# DIGITAL2.net
KiCad netlist of a schematic drawn in EAGLE
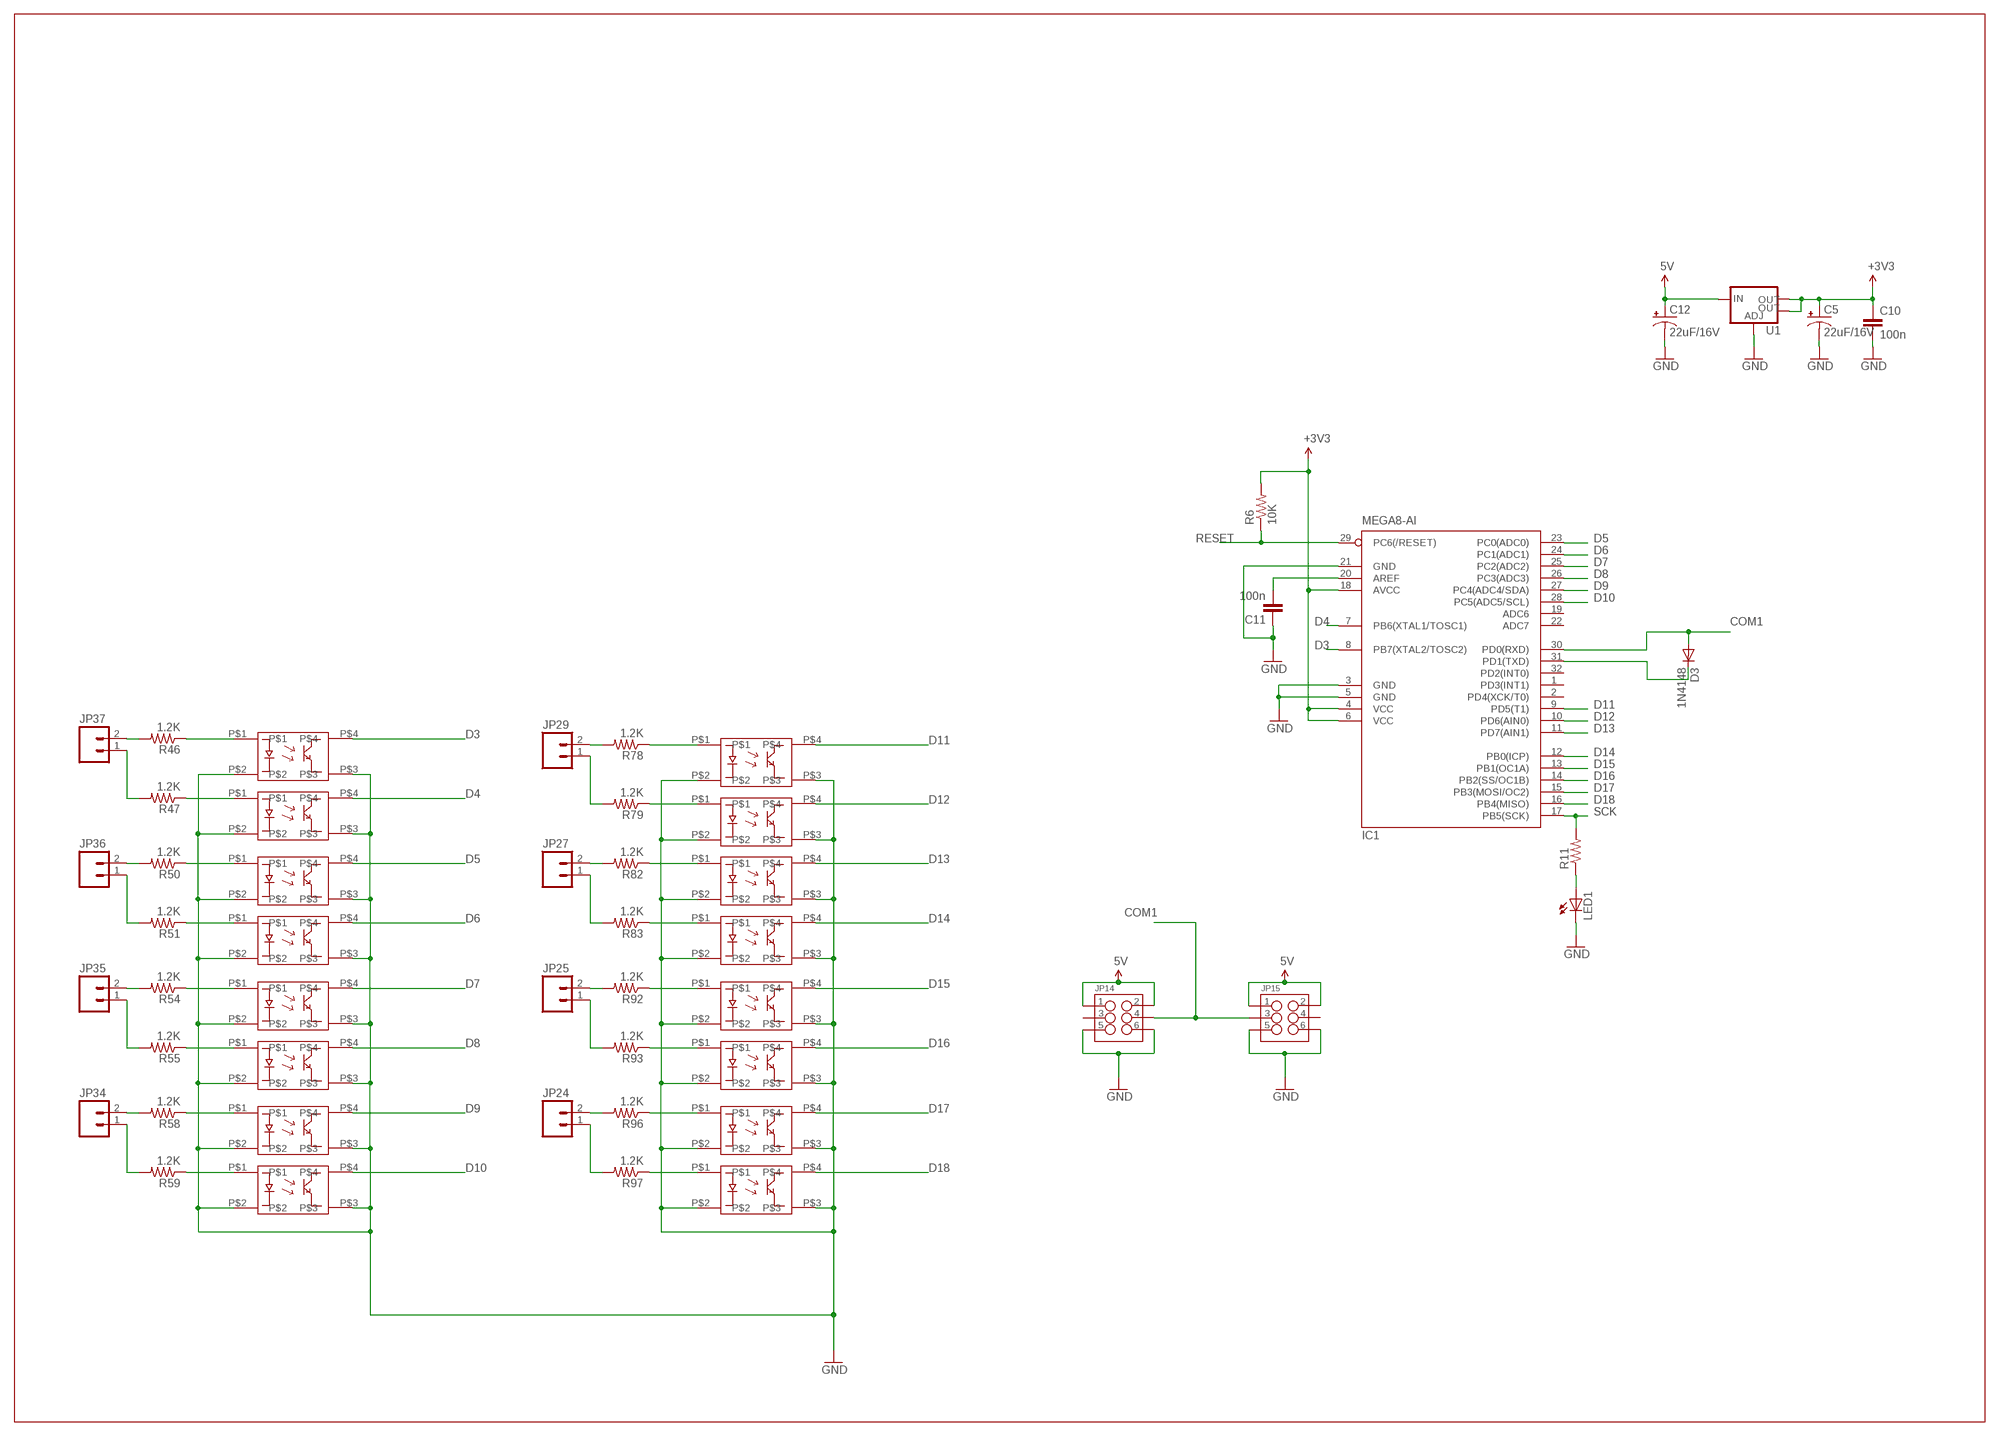
[diagram p0: schematic, sheet 1]

(export (version "E")
  (design (tool "Eeschema 10.0.6"))
  (components
    (comp (ref "C5")
      (value "22uF/16V")
      (footprint "eagle-import:EIA3216")
      (libsource (lib "eagle-import") (part "CAP_POL1206"))
    )
    (comp (ref "C10")
      (value "100n")
      (footprint "eagle-import:0805")
      (libsource (lib "eagle-import") (part "CAP0805"))
    )
    (comp (ref "C11")
      (value "100n")
      (footprint "eagle-import:0805")
      (libsource (lib "eagle-import") (part "CAP0805"))
    )
    (comp (ref "C12")
      (value "22uF/16V")
      (footprint "eagle-import:EIA3216")
      (libsource (lib "eagle-import") (part "CAP_POL1206"))
    )
    (comp (ref "D3")
      (value "1N4148")
      (footprint "eagle-import:MINIMELF")
      (libsource (lib "eagle-import") (part "DIODE-MINIMELF"))
    )
    (comp (ref "IC1")
      (value "MEGA8-AI")
      (footprint "eagle-import:TQFP32-08")
      (fields (field (name "MPN") "ATMEGA8-16AU"))
      (libsource (lib "eagle-import") (part "MEGA8-AI"))
    )
    (comp (ref "JP14")
      (value "M03X22X3_SILK_MALE_PTH")
      (footprint "eagle-import:2X3")
      (libsource (lib "eagle-import") (part "M03X22X3_SILK_MALE_PTH"))
    )
    (comp (ref "JP15")
      (value "M03X22X3_SILK_MALE_PTH")
      (footprint "eagle-import:2X3")
      (libsource (lib "eagle-import") (part "M03X22X3_SILK_MALE_PTH"))
    )
    (comp (ref "JP24")
      (value "M025MM")
      (footprint "eagle-import:SCREWTERMINAL-5MM-2")
      (libsource (lib "eagle-import") (part "M025MM"))
    )
    (comp (ref "JP25")
      (value "M025MM")
      (footprint "eagle-import:SCREWTERMINAL-5MM-2")
      (libsource (lib "eagle-import") (part "M025MM"))
    )
    (comp (ref "JP27")
      (value "M025MM")
      (footprint "eagle-import:SCREWTERMINAL-5MM-2")
      (libsource (lib "eagle-import") (part "M025MM"))
    )
    (comp (ref "JP29")
      (value "M025MM")
      (footprint "eagle-import:SCREWTERMINAL-5MM-2")
      (libsource (lib "eagle-import") (part "M025MM"))
    )
    (comp (ref "JP34")
      (value "M025MM")
      (footprint "eagle-import:SCREWTERMINAL-5MM-2")
      (libsource (lib "eagle-import") (part "M025MM"))
    )
    (comp (ref "JP35")
      (value "M025MM")
      (footprint "eagle-import:SCREWTERMINAL-5MM-2")
      (libsource (lib "eagle-import") (part "M025MM"))
    )
    (comp (ref "JP36")
      (value "M025MM")
      (footprint "eagle-import:SCREWTERMINAL-5MM-2")
      (libsource (lib "eagle-import") (part "M025MM"))
    )
    (comp (ref "JP37")
      (value "M025MM")
      (footprint "eagle-import:SCREWTERMINAL-5MM-2")
      (libsource (lib "eagle-import") (part "M025MM"))
    )
    (comp (ref "LED1")
      (value "LEDCHIP-LED0805")
      (footprint "eagle-import:CHIP-LED0805")
      (libsource (lib "eagle-import") (part "LEDCHIP-LED0805"))
    )
    (comp (ref "R6")
      (value "10K")
      (footprint "eagle-import:0805")
      (libsource (lib "eagle-import") (part "RESISTOR0805-RES"))
    )
    (comp (ref "R11")
      (value "RESISTOR0805-RES")
      (footprint "eagle-import:0805")
      (libsource (lib "eagle-import") (part "RESISTOR0805-RES"))
    )
    (comp (ref "R46")
      (value "1.2K")
      (footprint "eagle-import:1206")
      (libsource (lib "eagle-import") (part "RESISTOR1206"))
    )
    (comp (ref "R47")
      (value "1.2K")
      (footprint "eagle-import:1206")
      (libsource (lib "eagle-import") (part "RESISTOR1206"))
    )
    (comp (ref "R50")
      (value "1.2K")
      (footprint "eagle-import:1206")
      (libsource (lib "eagle-import") (part "RESISTOR1206"))
    )
    (comp (ref "R51")
      (value "1.2K")
      (footprint "eagle-import:1206")
      (libsource (lib "eagle-import") (part "RESISTOR1206"))
    )
    (comp (ref "R54")
      (value "1.2K")
      (footprint "eagle-import:1206")
      (libsource (lib "eagle-import") (part "RESISTOR1206"))
    )
    (comp (ref "R55")
      (value "1.2K")
      (footprint "eagle-import:1206")
      (libsource (lib "eagle-import") (part "RESISTOR1206"))
    )
    (comp (ref "R58")
      (value "1.2K")
      (footprint "eagle-import:1206")
      (libsource (lib "eagle-import") (part "RESISTOR1206"))
    )
    (comp (ref "R59")
      (value "1.2K")
      (footprint "eagle-import:1206")
      (libsource (lib "eagle-import") (part "RESISTOR1206"))
    )
    (comp (ref "R78")
      (value "1.2K")
      (footprint "eagle-import:1206")
      (libsource (lib "eagle-import") (part "RESISTOR1206"))
    )
    (comp (ref "R79")
      (value "1.2K")
      (footprint "eagle-import:1206")
      (libsource (lib "eagle-import") (part "RESISTOR1206"))
    )
    (comp (ref "R82")
      (value "1.2K")
      (footprint "eagle-import:1206")
      (libsource (lib "eagle-import") (part "RESISTOR1206"))
    )
    (comp (ref "R83")
      (value "1.2K")
      (footprint "eagle-import:1206")
      (libsource (lib "eagle-import") (part "RESISTOR1206"))
    )
    (comp (ref "R92")
      (value "1.2K")
      (footprint "eagle-import:1206")
      (libsource (lib "eagle-import") (part "RESISTOR1206"))
    )
    (comp (ref "R93")
      (value "1.2K")
      (footprint "eagle-import:1206")
      (libsource (lib "eagle-import") (part "RESISTOR1206"))
    )
    (comp (ref "R96")
      (value "1.2K")
      (footprint "eagle-import:1206")
      (libsource (lib "eagle-import") (part "RESISTOR1206"))
    )
    (comp (ref "R97")
      (value "1.2K")
      (footprint "eagle-import:1206")
      (libsource (lib "eagle-import") (part "RESISTOR1206"))
    )
    (comp (ref "U$13")
      (value "IS181D-I")
      (footprint "eagle-import:TLP181-I")
      (libsource (lib "eagle-import") (part "IS181D-I"))
    )
    (comp (ref "U$14")
      (value "IS181D-I")
      (footprint "eagle-import:TLP181-I")
      (libsource (lib "eagle-import") (part "IS181D-I"))
    )
    (comp (ref "U$15")
      (value "IS181D-I")
      (footprint "eagle-import:TLP181-I")
      (libsource (lib "eagle-import") (part "IS181D-I"))
    )
    (comp (ref "U$16")
      (value "IS181D-I")
      (footprint "eagle-import:TLP181-I")
      (libsource (lib "eagle-import") (part "IS181D-I"))
    )
    (comp (ref "U$17")
      (value "IS181D-I")
      (footprint "eagle-import:TLP181-I")
      (libsource (lib "eagle-import") (part "IS181D-I"))
    )
    (comp (ref "U$18")
      (value "IS181D-I")
      (footprint "eagle-import:TLP181-I")
      (libsource (lib "eagle-import") (part "IS181D-I"))
    )
    (comp (ref "U$19")
      (value "IS181D-I")
      (footprint "eagle-import:TLP181-I")
      (libsource (lib "eagle-import") (part "IS181D-I"))
    )
    (comp (ref "U$20")
      (value "IS181D-I")
      (footprint "eagle-import:TLP181-I")
      (libsource (lib "eagle-import") (part "IS181D-I"))
    )
    (comp (ref "U$29")
      (value "IS181D-I")
      (footprint "eagle-import:TLP181-I")
      (libsource (lib "eagle-import") (part "IS181D-I"))
    )
    (comp (ref "U$30")
      (value "IS181D-I")
      (footprint "eagle-import:TLP181-I")
      (libsource (lib "eagle-import") (part "IS181D-I"))
    )
    (comp (ref "U$31")
      (value "IS181D-I")
      (footprint "eagle-import:TLP181-I")
      (libsource (lib "eagle-import") (part "IS181D-I"))
    )
    (comp (ref "U$32")
      (value "IS181D-I")
      (footprint "eagle-import:TLP181-I")
      (libsource (lib "eagle-import") (part "IS181D-I"))
    )
    (comp (ref "U$33")
      (value "IS181D-I")
      (footprint "eagle-import:TLP181-I")
      (libsource (lib "eagle-import") (part "IS181D-I"))
    )
    (comp (ref "U$34")
      (value "IS181D-I")
      (footprint "eagle-import:TLP181-I")
      (libsource (lib "eagle-import") (part "IS181D-I"))
    )
    (comp (ref "U$35")
      (value "IS181D-I")
      (footprint "eagle-import:TLP181-I")
      (libsource (lib "eagle-import") (part "IS181D-I"))
    )
    (comp (ref "U$36")
      (value "IS181D-I")
      (footprint "eagle-import:TLP181-I")
      (libsource (lib "eagle-import") (part "IS181D-I"))
    )
    (comp (ref "U1")
      (value "V_REG_LM1117SOT223")
      (footprint "eagle-import:SOT223")
      (libsource (lib "eagle-import") (part "V_REG_LM1117SOT223"))
    )
  )
  (nets
    (net (code "1") (name "+3V3") (class "Default")
      (node (ref "C10") (pin "1") (pinfunction "1_1") (pintype "passive"))
      (node (ref "C5") (pin "A") (pinfunction "+_A") (pintype "passive"))
      (node (ref "IC1") (pin "18") (pinfunction "AVCC_18") (pintype "power_in"))
      (node (ref "IC1") (pin "4") (pinfunction "VCC_4") (pintype "power_in"))
      (node (ref "IC1") (pin "6") (pinfunction "VCC_6") (pintype "power_in"))
      (node (ref "R6") (pin "2") (pinfunction "2_2") (pintype "passive"))
      (node (ref "U1") (pin "2") (pinfunction "OUT_2") (pintype "output"))
      (node (ref "U1") (pin "4") (pinfunction "OUT_4") (pintype "output"))
    )
    (net (code "2") (name "/COM1") (class "Default")
      (node (ref "D3") (pin "A") (pinfunction "A_A") (pintype "passive"))
      (node (ref "IC1") (pin "30") (pinfunction "PD0(RXD)_30") (pintype "bidirectional"))
      (node (ref "JP14") (pin "4") (pinfunction "4_4") (pintype "bidirectional"))
      (node (ref "JP15") (pin "3") (pinfunction "3_3") (pintype "bidirectional"))
    )
    (net (code "3") (name "/D3") (class "Default")
      (node (ref "IC1") (pin "8") (pinfunction "PB7(XTAL2/TOSC2)_8") (pintype "bidirectional"))
      (node (ref "U$13") (pin "P$4") (pinfunction "P$4_P$4") (pintype "bidirectional"))
    )
    (net (code "4") (name "/D4") (class "Default")
      (node (ref "IC1") (pin "7") (pinfunction "PB6(XTAL1/TOSC1)_7") (pintype "bidirectional"))
      (node (ref "U$14") (pin "P$4") (pinfunction "P$4_P$4") (pintype "bidirectional"))
    )
    (net (code "5") (name "/D5") (class "Default")
      (node (ref "IC1") (pin "23") (pinfunction "PC0(ADC0)_23") (pintype "bidirectional"))
      (node (ref "U$15") (pin "P$4") (pinfunction "P$4_P$4") (pintype "bidirectional"))
    )
    (net (code "6") (name "/D6") (class "Default")
      (node (ref "IC1") (pin "24") (pinfunction "PC1(ADC1)_24") (pintype "bidirectional"))
      (node (ref "U$16") (pin "P$4") (pinfunction "P$4_P$4") (pintype "bidirectional"))
    )
    (net (code "7") (name "/D7") (class "Default")
      (node (ref "IC1") (pin "25") (pinfunction "PC2(ADC2)_25") (pintype "bidirectional"))
      (node (ref "U$17") (pin "P$4") (pinfunction "P$4_P$4") (pintype "bidirectional"))
    )
    (net (code "8") (name "/D8") (class "Default")
      (node (ref "IC1") (pin "26") (pinfunction "PC3(ADC3)_26") (pintype "bidirectional"))
      (node (ref "U$18") (pin "P$4") (pinfunction "P$4_P$4") (pintype "bidirectional"))
    )
    (net (code "9") (name "/D9") (class "Default")
      (node (ref "IC1") (pin "27") (pinfunction "PC4(ADC4/SDA)_27") (pintype "bidirectional"))
      (node (ref "U$19") (pin "P$4") (pinfunction "P$4_P$4") (pintype "bidirectional"))
    )
    (net (code "10") (name "/D10") (class "Default")
      (node (ref "IC1") (pin "28") (pinfunction "PC5(ADC5/SCL)_28") (pintype "bidirectional"))
      (node (ref "U$20") (pin "P$4") (pinfunction "P$4_P$4") (pintype "bidirectional"))
    )
    (net (code "11") (name "/D11") (class "Default")
      (node (ref "IC1") (pin "9") (pinfunction "PD5(T1)_9") (pintype "bidirectional"))
      (node (ref "U$29") (pin "P$4") (pinfunction "P$4_P$4") (pintype "bidirectional"))
    )
    (net (code "12") (name "/D12") (class "Default")
      (node (ref "IC1") (pin "10") (pinfunction "PD6(AIN0)_10") (pintype "bidirectional"))
      (node (ref "U$30") (pin "P$4") (pinfunction "P$4_P$4") (pintype "bidirectional"))
    )
    (net (code "13") (name "/D13") (class "Default")
      (node (ref "IC1") (pin "11") (pinfunction "PD7(AIN1)_11") (pintype "bidirectional"))
      (node (ref "U$31") (pin "P$4") (pinfunction "P$4_P$4") (pintype "bidirectional"))
    )
    (net (code "14") (name "/D14") (class "Default")
      (node (ref "IC1") (pin "12") (pinfunction "PB0(ICP)_12") (pintype "bidirectional"))
      (node (ref "U$32") (pin "P$4") (pinfunction "P$4_P$4") (pintype "bidirectional"))
    )
    (net (code "15") (name "/D15") (class "Default")
      (node (ref "IC1") (pin "13") (pinfunction "PB1(OC1A)_13") (pintype "bidirectional"))
      (node (ref "U$33") (pin "P$4") (pinfunction "P$4_P$4") (pintype "bidirectional"))
    )
    (net (code "16") (name "/D16") (class "Default")
      (node (ref "IC1") (pin "14") (pinfunction "PB2(SS/OC1B)_14") (pintype "bidirectional"))
      (node (ref "U$34") (pin "P$4") (pinfunction "P$4_P$4") (pintype "bidirectional"))
    )
    (net (code "17") (name "/D17") (class "Default")
      (node (ref "IC1") (pin "15") (pinfunction "PB3(MOSI/OC2)_15") (pintype "bidirectional"))
      (node (ref "U$35") (pin "P$4") (pinfunction "P$4_P$4") (pintype "bidirectional"))
    )
    (net (code "18") (name "/D18") (class "Default")
      (node (ref "IC1") (pin "16") (pinfunction "PB4(MISO)_16") (pintype "bidirectional"))
      (node (ref "U$36") (pin "P$4") (pinfunction "P$4_P$4") (pintype "bidirectional"))
    )
    (net (code "19") (name "/RESET") (class "Default")
      (node (ref "IC1") (pin "29") (pinfunction "PC6(/RESET)_29") (pintype "bidirectional"))
      (node (ref "R6") (pin "1") (pinfunction "1_1") (pintype "passive"))
    )
    (net (code "20") (name "/SCK") (class "Default")
      (node (ref "IC1") (pin "17") (pinfunction "PB5(SCK)_17") (pintype "bidirectional"))
      (node (ref "R11") (pin "2") (pinfunction "2_2") (pintype "passive"))
    )
    (net (code "21") (name "5V") (class "Default")
      (node (ref "C12") (pin "A") (pinfunction "+_A") (pintype "passive"))
      (node (ref "JP14") (pin "1") (pinfunction "1_1") (pintype "bidirectional"))
      (node (ref "JP14") (pin "2") (pinfunction "2_2") (pintype "bidirectional"))
      (node (ref "JP15") (pin "1") (pinfunction "1_1") (pintype "bidirectional"))
      (node (ref "JP15") (pin "2") (pinfunction "2_2") (pintype "bidirectional"))
      (node (ref "U1") (pin "3") (pinfunction "IN_3") (pintype "input"))
    )
    (net (code "22") (name "GND") (class "Default")
      (node (ref "C10") (pin "2") (pinfunction "2_2") (pintype "passive"))
      (node (ref "C11") (pin "1") (pinfunction "1_1") (pintype "passive"))
      (node (ref "C12") (pin "C") (pinfunction "-_C") (pintype "passive"))
      (node (ref "C5") (pin "C") (pinfunction "-_C") (pintype "passive"))
      (node (ref "IC1") (pin "21") (pinfunction "GND_21") (pintype "power_in"))
      (node (ref "IC1") (pin "3") (pinfunction "GND_3") (pintype "power_in"))
      (node (ref "IC1") (pin "5") (pinfunction "GND_5") (pintype "power_in"))
      (node (ref "JP14") (pin "5") (pinfunction "5_5") (pintype "bidirectional"))
      (node (ref "JP14") (pin "6") (pinfunction "6_6") (pintype "bidirectional"))
      (node (ref "JP15") (pin "5") (pinfunction "5_5") (pintype "bidirectional"))
      (node (ref "JP15") (pin "6") (pinfunction "6_6") (pintype "bidirectional"))
      (node (ref "LED1") (pin "C") (pinfunction "C_C") (pintype "passive"))
      (node (ref "U$13") (pin "P$2") (pinfunction "P$2_P$2") (pintype "bidirectional"))
      (node (ref "U$13") (pin "P$3") (pinfunction "P$3_P$3") (pintype "bidirectional"))
      (node (ref "U$14") (pin "P$2") (pinfunction "P$2_P$2") (pintype "bidirectional"))
      (node (ref "U$14") (pin "P$3") (pinfunction "P$3_P$3") (pintype "bidirectional"))
      (node (ref "U$15") (pin "P$2") (pinfunction "P$2_P$2") (pintype "bidirectional"))
      (node (ref "U$15") (pin "P$3") (pinfunction "P$3_P$3") (pintype "bidirectional"))
      (node (ref "U$16") (pin "P$2") (pinfunction "P$2_P$2") (pintype "bidirectional"))
      (node (ref "U$16") (pin "P$3") (pinfunction "P$3_P$3") (pintype "bidirectional"))
      (node (ref "U$17") (pin "P$2") (pinfunction "P$2_P$2") (pintype "bidirectional"))
      (node (ref "U$17") (pin "P$3") (pinfunction "P$3_P$3") (pintype "bidirectional"))
      (node (ref "U$18") (pin "P$2") (pinfunction "P$2_P$2") (pintype "bidirectional"))
      (node (ref "U$18") (pin "P$3") (pinfunction "P$3_P$3") (pintype "bidirectional"))
      (node (ref "U$19") (pin "P$2") (pinfunction "P$2_P$2") (pintype "bidirectional"))
      (node (ref "U$19") (pin "P$3") (pinfunction "P$3_P$3") (pintype "bidirectional"))
      (node (ref "U$20") (pin "P$2") (pinfunction "P$2_P$2") (pintype "bidirectional"))
      (node (ref "U$20") (pin "P$3") (pinfunction "P$3_P$3") (pintype "bidirectional"))
      (node (ref "U$29") (pin "P$2") (pinfunction "P$2_P$2") (pintype "bidirectional"))
      (node (ref "U$29") (pin "P$3") (pinfunction "P$3_P$3") (pintype "bidirectional"))
      (node (ref "U$30") (pin "P$2") (pinfunction "P$2_P$2") (pintype "bidirectional"))
      (node (ref "U$30") (pin "P$3") (pinfunction "P$3_P$3") (pintype "bidirectional"))
      (node (ref "U$31") (pin "P$2") (pinfunction "P$2_P$2") (pintype "bidirectional"))
      (node (ref "U$31") (pin "P$3") (pinfunction "P$3_P$3") (pintype "bidirectional"))
      (node (ref "U$32") (pin "P$2") (pinfunction "P$2_P$2") (pintype "bidirectional"))
      (node (ref "U$32") (pin "P$3") (pinfunction "P$3_P$3") (pintype "bidirectional"))
      (node (ref "U$33") (pin "P$2") (pinfunction "P$2_P$2") (pintype "bidirectional"))
      (node (ref "U$33") (pin "P$3") (pinfunction "P$3_P$3") (pintype "bidirectional"))
      (node (ref "U$34") (pin "P$2") (pinfunction "P$2_P$2") (pintype "bidirectional"))
      (node (ref "U$34") (pin "P$3") (pinfunction "P$3_P$3") (pintype "bidirectional"))
      (node (ref "U$35") (pin "P$2") (pinfunction "P$2_P$2") (pintype "bidirectional"))
      (node (ref "U$35") (pin "P$3") (pinfunction "P$3_P$3") (pintype "bidirectional"))
      (node (ref "U$36") (pin "P$2") (pinfunction "P$2_P$2") (pintype "bidirectional"))
      (node (ref "U$36") (pin "P$3") (pinfunction "P$3_P$3") (pintype "bidirectional"))
      (node (ref "U1") (pin "1") (pinfunction "ADJ_1") (pintype "input"))
    )
    (net (code "23") (name "Net-(IC1-AREF)") (class "Default")
      (node (ref "C11") (pin "2") (pinfunction "2_2") (pintype "passive"))
      (node (ref "IC1") (pin "20") (pinfunction "AREF_20") (pintype "passive"))
    )
    (net (code "24") (name "Net-(IC1-PD1(TXD))") (class "Default")
      (node (ref "D3") (pin "C") (pinfunction "C_C") (pintype "passive"))
      (node (ref "IC1") (pin "31") (pinfunction "PD1(TXD)_31") (pintype "bidirectional"))
    )
    (net (code "25") (name "Net-(JP24-Pad1)") (class "Default")
      (node (ref "JP24") (pin "1") (pinfunction "1_1") (pintype "passive"))
      (node (ref "R97") (pin "2") (pinfunction "2_2") (pintype "passive"))
    )
    (net (code "26") (name "Net-(JP24-Pad2)") (class "Default")
      (node (ref "JP24") (pin "2") (pinfunction "2_2") (pintype "passive"))
      (node (ref "R96") (pin "2") (pinfunction "2_2") (pintype "passive"))
    )
    (net (code "27") (name "Net-(JP25-Pad1)") (class "Default")
      (node (ref "JP25") (pin "1") (pinfunction "1_1") (pintype "passive"))
      (node (ref "R93") (pin "2") (pinfunction "2_2") (pintype "passive"))
    )
    (net (code "28") (name "Net-(JP25-Pad2)") (class "Default")
      (node (ref "JP25") (pin "2") (pinfunction "2_2") (pintype "passive"))
      (node (ref "R92") (pin "2") (pinfunction "2_2") (pintype "passive"))
    )
    (net (code "29") (name "Net-(JP27-Pad1)") (class "Default")
      (node (ref "JP27") (pin "1") (pinfunction "1_1") (pintype "passive"))
      (node (ref "R83") (pin "2") (pinfunction "2_2") (pintype "passive"))
    )
    (net (code "30") (name "Net-(JP27-Pad2)") (class "Default")
      (node (ref "JP27") (pin "2") (pinfunction "2_2") (pintype "passive"))
      (node (ref "R82") (pin "2") (pinfunction "2_2") (pintype "passive"))
    )
    (net (code "31") (name "Net-(JP29-Pad1)") (class "Default")
      (node (ref "JP29") (pin "1") (pinfunction "1_1") (pintype "passive"))
      (node (ref "R79") (pin "2") (pinfunction "2_2") (pintype "passive"))
    )
    (net (code "32") (name "Net-(JP29-Pad2)") (class "Default")
      (node (ref "JP29") (pin "2") (pinfunction "2_2") (pintype "passive"))
      (node (ref "R78") (pin "2") (pinfunction "2_2") (pintype "passive"))
    )
    (net (code "33") (name "Net-(JP34-Pad1)") (class "Default")
      (node (ref "JP34") (pin "1") (pinfunction "1_1") (pintype "passive"))
      (node (ref "R59") (pin "2") (pinfunction "2_2") (pintype "passive"))
    )
    (net (code "34") (name "Net-(JP34-Pad2)") (class "Default")
      (node (ref "JP34") (pin "2") (pinfunction "2_2") (pintype "passive"))
      (node (ref "R58") (pin "2") (pinfunction "2_2") (pintype "passive"))
    )
    (net (code "35") (name "Net-(JP35-Pad1)") (class "Default")
      (node (ref "JP35") (pin "1") (pinfunction "1_1") (pintype "passive"))
      (node (ref "R55") (pin "2") (pinfunction "2_2") (pintype "passive"))
    )
    (net (code "36") (name "Net-(JP35-Pad2)") (class "Default")
      (node (ref "JP35") (pin "2") (pinfunction "2_2") (pintype "passive"))
      (node (ref "R54") (pin "2") (pinfunction "2_2") (pintype "passive"))
    )
    (net (code "37") (name "Net-(JP36-Pad1)") (class "Default")
      (node (ref "JP36") (pin "1") (pinfunction "1_1") (pintype "passive"))
      (node (ref "R51") (pin "2") (pinfunction "2_2") (pintype "passive"))
    )
    (net (code "38") (name "Net-(JP36-Pad2)") (class "Default")
      (node (ref "JP36") (pin "2") (pinfunction "2_2") (pintype "passive"))
      (node (ref "R50") (pin "2") (pinfunction "2_2") (pintype "passive"))
    )
    (net (code "39") (name "Net-(JP37-Pad1)") (class "Default")
      (node (ref "JP37") (pin "1") (pinfunction "1_1") (pintype "passive"))
      (node (ref "R47") (pin "2") (pinfunction "2_2") (pintype "passive"))
    )
    (net (code "40") (name "Net-(JP37-Pad2)") (class "Default")
      (node (ref "JP37") (pin "2") (pinfunction "2_2") (pintype "passive"))
      (node (ref "R46") (pin "2") (pinfunction "2_2") (pintype "passive"))
    )
    (net (code "41") (name "Net-(LED1-PadA)") (class "Default")
      (node (ref "LED1") (pin "A") (pinfunction "A_A") (pintype "passive"))
      (node (ref "R11") (pin "1") (pinfunction "1_1") (pintype "passive"))
    )
    (net (code "42") (name "Net-(R46-Pad1)") (class "Default")
      (node (ref "R46") (pin "1") (pinfunction "1_1") (pintype "passive"))
      (node (ref "U$13") (pin "P$1") (pinfunction "P$1_P$1") (pintype "bidirectional"))
    )
    (net (code "43") (name "Net-(R47-Pad1)") (class "Default")
      (node (ref "R47") (pin "1") (pinfunction "1_1") (pintype "passive"))
      (node (ref "U$14") (pin "P$1") (pinfunction "P$1_P$1") (pintype "bidirectional"))
    )
    (net (code "44") (name "Net-(R50-Pad1)") (class "Default")
      (node (ref "R50") (pin "1") (pinfunction "1_1") (pintype "passive"))
      (node (ref "U$15") (pin "P$1") (pinfunction "P$1_P$1") (pintype "bidirectional"))
    )
    (net (code "45") (name "Net-(R51-Pad1)") (class "Default")
      (node (ref "R51") (pin "1") (pinfunction "1_1") (pintype "passive"))
      (node (ref "U$16") (pin "P$1") (pinfunction "P$1_P$1") (pintype "bidirectional"))
    )
    (net (code "46") (name "Net-(R54-Pad1)") (class "Default")
      (node (ref "R54") (pin "1") (pinfunction "1_1") (pintype "passive"))
      (node (ref "U$17") (pin "P$1") (pinfunction "P$1_P$1") (pintype "bidirectional"))
    )
    (net (code "47") (name "Net-(R55-Pad1)") (class "Default")
      (node (ref "R55") (pin "1") (pinfunction "1_1") (pintype "passive"))
      (node (ref "U$18") (pin "P$1") (pinfunction "P$1_P$1") (pintype "bidirectional"))
    )
    (net (code "48") (name "Net-(R58-Pad1)") (class "Default")
      (node (ref "R58") (pin "1") (pinfunction "1_1") (pintype "passive"))
      (node (ref "U$19") (pin "P$1") (pinfunction "P$1_P$1") (pintype "bidirectional"))
    )
    (net (code "49") (name "Net-(R59-Pad1)") (class "Default")
      (node (ref "R59") (pin "1") (pinfunction "1_1") (pintype "passive"))
      (node (ref "U$20") (pin "P$1") (pinfunction "P$1_P$1") (pintype "bidirectional"))
    )
    (net (code "50") (name "Net-(R78-Pad1)") (class "Default")
      (node (ref "R78") (pin "1") (pinfunction "1_1") (pintype "passive"))
      (node (ref "U$29") (pin "P$1") (pinfunction "P$1_P$1") (pintype "bidirectional"))
    )
    (net (code "51") (name "Net-(R79-Pad1)") (class "Default")
      (node (ref "R79") (pin "1") (pinfunction "1_1") (pintype "passive"))
      (node (ref "U$30") (pin "P$1") (pinfunction "P$1_P$1") (pintype "bidirectional"))
    )
    (net (code "52") (name "Net-(R82-Pad1)") (class "Default")
      (node (ref "R82") (pin "1") (pinfunction "1_1") (pintype "passive"))
      (node (ref "U$31") (pin "P$1") (pinfunction "P$1_P$1") (pintype "bidirectional"))
    )
    (net (code "53") (name "Net-(R83-Pad1)") (class "Default")
      (node (ref "R83") (pin "1") (pinfunction "1_1") (pintype "passive"))
      (node (ref "U$32") (pin "P$1") (pinfunction "P$1_P$1") (pintype "bidirectional"))
    )
    (net (code "54") (name "Net-(R92-Pad1)") (class "Default")
      (node (ref "R92") (pin "1") (pinfunction "1_1") (pintype "passive"))
      (node (ref "U$33") (pin "P$1") (pinfunction "P$1_P$1") (pintype "bidirectional"))
    )
    (net (code "55") (name "Net-(R93-Pad1)") (class "Default")
      (node (ref "R93") (pin "1") (pinfunction "1_1") (pintype "passive"))
      (node (ref "U$34") (pin "P$1") (pinfunction "P$1_P$1") (pintype "bidirectional"))
    )
    (net (code "56") (name "Net-(R96-Pad1)") (class "Default")
      (node (ref "R96") (pin "1") (pinfunction "1_1") (pintype "passive"))
      (node (ref "U$35") (pin "P$1") (pinfunction "P$1_P$1") (pintype "bidirectional"))
    )
    (net (code "57") (name "Net-(R97-Pad1)") (class "Default")
      (node (ref "R97") (pin "1") (pinfunction "1_1") (pintype "passive"))
      (node (ref "U$36") (pin "P$1") (pinfunction "P$1_P$1") (pintype "bidirectional"))
    )
    (net (code "58") (name "unconnected-(IC1-ADC6-Pad19)") (class "Default")
      (node (ref "IC1") (pin "19") (pinfunction "ADC6_19") (pintype "bidirectional"))
    )
    (net (code "59") (name "unconnected-(IC1-ADC7-Pad22)") (class "Default")
      (node (ref "IC1") (pin "22") (pinfunction "ADC7_22") (pintype "bidirectional"))
    )
    (net (code "60") (name "unconnected-(IC1-PD2(INT0)-Pad32)") (class "Default")
      (node (ref "IC1") (pin "32") (pinfunction "PD2(INT0)_32") (pintype "bidirectional"))
    )
    (net (code "61") (name "unconnected-(IC1-PD3(INT1)-Pad1)") (class "Default")
      (node (ref "IC1") (pin "1") (pinfunction "PD3(INT1)_1") (pintype "bidirectional"))
    )
    (net (code "62") (name "unconnected-(IC1-PD4(XCK{slash}T0)-Pad2)") (class "Default")
      (node (ref "IC1") (pin "2") (pinfunction "PD4(XCK/T0)_2") (pintype "bidirectional"))
    )
    (net (code "63") (name "unconnected-(JP14-Pad3)") (class "Default")
      (node (ref "JP14") (pin "3") (pinfunction "3_3") (pintype "bidirectional"))
    )
    (net (code "64") (name "unconnected-(JP15-Pad4)") (class "Default")
      (node (ref "JP15") (pin "4") (pinfunction "4_4") (pintype "bidirectional"))
    )
  )
)
